# BiodataFeatherProMicro_004.net
KiCad netlist of a schematic drawn in EAGLE
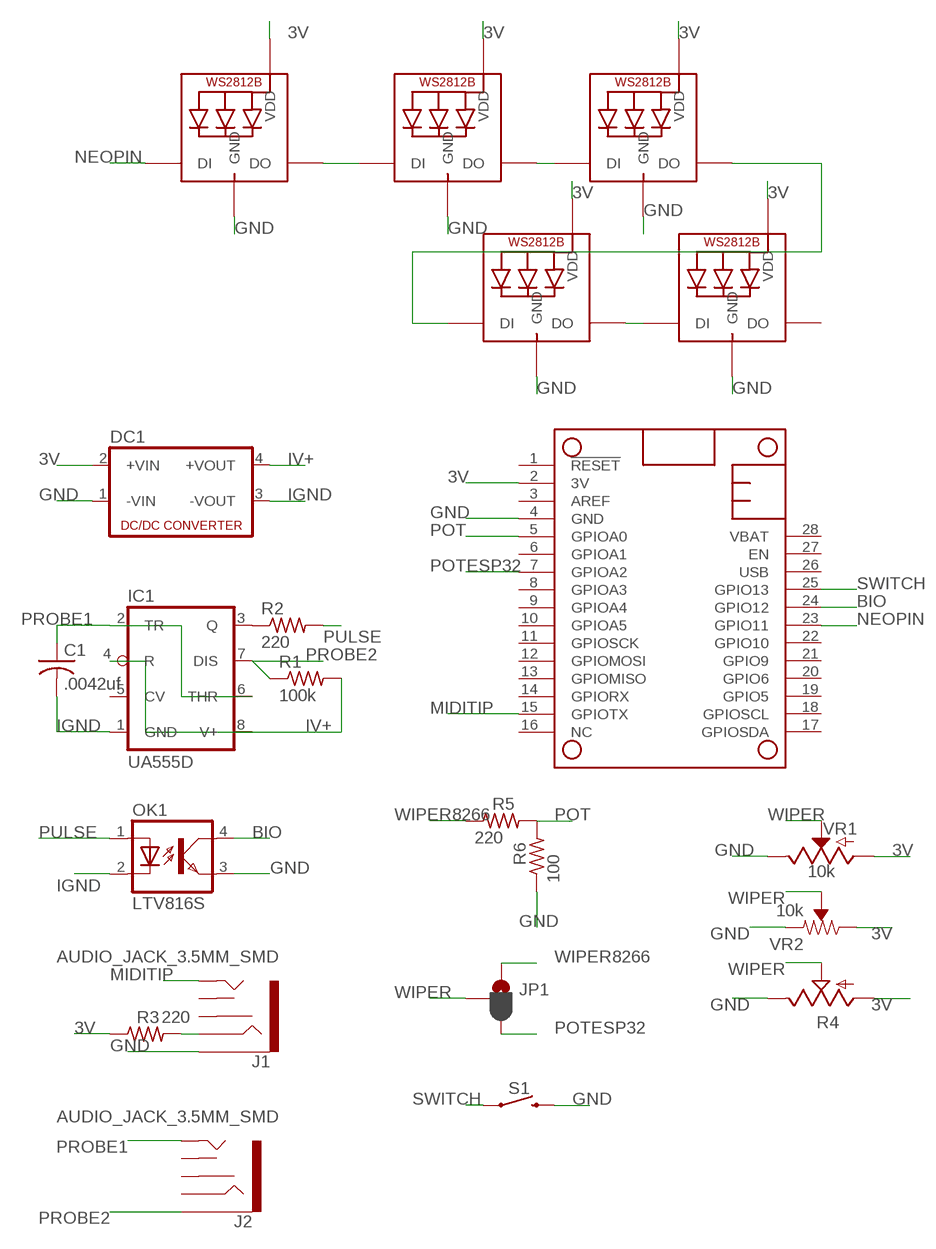
[diagram p0: schematic, sheet 1]

(export (version "E")
  (design (tool "Eeschema 10.0.6"))
  (components
    (comp (ref "C1")
      (value ".0042uf")
      (footprint "eagle-import:C1206")
      (libsource (lib "eagle-import") (part "C-USC1206"))
    )
    (comp (ref "DC1")
      (value "NME")
      (footprint "eagle-import:NME")
      (fields (field (name "MF") "C & D TECHNOLOGIES, INC") (field (name "MPN") "NME1205D"))
      (libsource (lib "eagle-import") (part "NME"))
    )
    (comp (ref "IC1")
      (value "UA555D")
      (footprint "eagle-import:SO08")
      (libsource (lib "eagle-import") (part "555DUA"))
    )
    (comp (ref "J1")
      (value "AUDIO_JACK_3.5MM_SMD")
      (footprint "eagle-import:AUDIO-JACK-3.5MM-SMD")
      (libsource (lib "eagle-import") (part "AUDIO_JACK_3.5MM_SMD"))
    )
    (comp (ref "J2")
      (value "AUDIO_JACK_3.5MM_SMD")
      (footprint "eagle-import:AUDIO-JACK-3.5MM-SMD")
      (libsource (lib "eagle-import") (part "AUDIO_JACK_3.5MM_SMD"))
    )
    (comp (ref "JP1")
      (value "JUMPER-SMT_3_1-NC_PASTE_SILK")
      (footprint "eagle-import:SMT-JUMPER_3_1-NC_PASTE_SILK")
      (libsource (lib "eagle-import") (part "JUMPER-SMT_3_1-NC_PASTE_SILK"))
    )
    (comp (ref "LED1")
      (value "WS2812B5050")
      (footprint "eagle-import:WS2812B")
      (libsource (lib "eagle-import") (part "WS2812B5050"))
    )
    (comp (ref "LED2")
      (value "WS2812B5050")
      (footprint "eagle-import:WS2812B")
      (libsource (lib "eagle-import") (part "WS2812B5050"))
    )
    (comp (ref "LED3")
      (value "WS2812B5050")
      (footprint "eagle-import:WS2812B")
      (libsource (lib "eagle-import") (part "WS2812B5050"))
    )
    (comp (ref "LED4")
      (value "WS2812B5050")
      (footprint "eagle-import:WS2812B")
      (libsource (lib "eagle-import") (part "WS2812B5050"))
    )
    (comp (ref "LED5")
      (value "WS2812B5050")
      (footprint "eagle-import:WS2812B")
      (libsource (lib "eagle-import") (part "WS2812B5050"))
    )
    (comp (ref "MS1")
      (value "FEATHERWING")
      (footprint "eagle-import:FEATHERWING_NOHOLES")
      (libsource (lib "eagle-import") (part "FEATHERWING"))
    )
    (comp (ref "OK1")
      (value "LTV816S")
      (footprint "eagle-import:SMD4")
      (libsource (lib "eagle-import") (part "LTV816S"))
    )
    (comp (ref "R1")
      (value "100k")
      (footprint "eagle-import:M1206")
      (libsource (lib "eagle-import") (part "R-US_M1206"))
    )
    (comp (ref "R2")
      (value "220")
      (footprint "eagle-import:M1206")
      (libsource (lib "eagle-import") (part "R-US_M1206"))
    )
    (comp (ref "R3")
      (value "220")
      (footprint "eagle-import:M1206")
      (libsource (lib "eagle-import") (part "R-US_M1206"))
    )
    (comp (ref "R4")
      (value "TRIM_US-S63P")
      (footprint "eagle-import:S63P")
      (libsource (lib "eagle-import") (part "TRIM_US-S63P"))
    )
    (comp (ref "R5")
      (value "220")
      (footprint "eagle-import:M1206")
      (libsource (lib "eagle-import") (part "R-US_M1206"))
    )
    (comp (ref "R6")
      (value "100")
      (footprint "eagle-import:M1206")
      (libsource (lib "eagle-import") (part "R-US_M1206"))
    )
    (comp (ref "S1")
      (value "MOMENTARY-SWITCH-SPST-PTH-6.0MM")
      (footprint "eagle-import:TACTILE_SWITCH_PTH_6.0MM")
      (libsource (lib "eagle-import") (part "MOMENTARY-SWITCH-SPST-PTH-6.0MM"))
    )
    (comp (ref "VR1")
      (value "10k")
      (footprint "eagle-import:POT-PTH-ALPS-KIT")
      (libsource (lib "eagle-import") (part "POTENTIOMETER-PTH-9MM-1/20W-20%-KIT"))
    )
    (comp (ref "VR2")
      (value "10k")
      (footprint "eagle-import:TRIMPOT-PTH-3386U")
      (libsource (lib "eagle-import") (part "TRIMPOT-PTH-10MM-KNOB-1/2W-10%"))
    )
  )
  (nets
    (net (code "1") (name "/3V") (class "Default")
      (node (ref "DC1") (pin "2") (pinfunction "+VIN_2") (pintype "passive"))
      (node (ref "LED1") (pin "1-VDD") (pinfunction "VDD_1-VDD") (pintype "power_in"))
      (node (ref "LED2") (pin "1-VDD") (pinfunction "VDD_1-VDD") (pintype "power_in"))
      (node (ref "LED3") (pin "1-VDD") (pinfunction "VDD_1-VDD") (pintype "power_in"))
      (node (ref "LED4") (pin "1-VDD") (pinfunction "VDD_1-VDD") (pintype "power_in"))
      (node (ref "LED5") (pin "1-VDD") (pinfunction "VDD_1-VDD") (pintype "power_in"))
      (node (ref "MS1") (pin "2") (pinfunction "3V_2") (pintype "power_in"))
      (node (ref "R3") (pin "1") (pinfunction "1_1") (pintype "passive"))
      (node (ref "R4") (pin "A") (pinfunction "A_A") (pintype "passive"))
      (node (ref "VR1") (pin "P$3") (pinfunction "A_P$3") (pintype "passive"))
      (node (ref "VR2") (pin "3") (pinfunction "CW_3") (pintype "passive"))
    )
    (net (code "2") (name "/BIO") (class "Default")
      (node (ref "MS1") (pin "24") (pinfunction "GPIO12_24") (pintype "bidirectional"))
      (node (ref "OK1") (pin "4") (pinfunction "COL_4") (pintype "passive"))
    )
    (net (code "3") (name "/GND") (class "Default")
      (node (ref "DC1") (pin "1") (pinfunction "-VIN_1") (pintype "passive"))
      (node (ref "J1") (pin "SLEEVE") (pinfunction "SLEEVE_SLEEVE") (pintype "bidirectional"))
      (node (ref "LED1") (pin "3-GND") (pinfunction "GND_3-GND") (pintype "power_in"))
      (node (ref "LED2") (pin "3-GND") (pinfunction "GND_3-GND") (pintype "power_in"))
      (node (ref "LED3") (pin "3-GND") (pinfunction "GND_3-GND") (pintype "power_in"))
      (node (ref "LED4") (pin "3-GND") (pinfunction "GND_3-GND") (pintype "power_in"))
      (node (ref "LED5") (pin "3-GND") (pinfunction "GND_3-GND") (pintype "power_in"))
      (node (ref "MS1") (pin "4") (pinfunction "GND_4") (pintype "power_in"))
      (node (ref "OK1") (pin "3") (pinfunction "EMIT_3") (pintype "passive"))
      (node (ref "R4") (pin "E") (pinfunction "E_E") (pintype "passive"))
      (node (ref "R6") (pin "1") (pinfunction "1_1") (pintype "passive"))
      (node (ref "S1") (pin "3") (pinfunction "2_3") (pintype "passive"))
      (node (ref "VR1") (pin "P$1") (pinfunction "E_P$1") (pintype "passive"))
      (node (ref "VR2") (pin "1") (pinfunction "CCW_1") (pintype "passive"))
    )
    (net (code "4") (name "/IGND") (class "Default")
      (node (ref "C1") (pin "2") (pinfunction "2_2") (pintype "passive"))
      (node (ref "DC1") (pin "3") (pinfunction "-VOUT_3") (pintype "passive"))
      (node (ref "IC1") (pin "1") (pinfunction "GND_1") (pintype "power_in"))
      (node (ref "OK1") (pin "2") (pinfunction "C_2") (pintype "passive"))
    )
    (net (code "5") (name "/IV+") (class "Default")
      (node (ref "DC1") (pin "4") (pinfunction "+VOUT_4") (pintype "passive"))
      (node (ref "IC1") (pin "4") (pinfunction "R_4") (pintype "input"))
      (node (ref "IC1") (pin "8") (pinfunction "V+_8") (pintype "power_in"))
      (node (ref "R1") (pin "2") (pinfunction "2_2") (pintype "passive"))
    )
    (net (code "6") (name "/MIDITIP") (class "Default")
      (node (ref "J1") (pin "TIP") (pinfunction "TIP_TIP") (pintype "bidirectional"))
      (node (ref "MS1") (pin "15") (pinfunction "GPIOTX_15") (pintype "bidirectional"))
    )
    (net (code "7") (name "/NEOPIN") (class "Default")
      (node (ref "LED1") (pin "4-DIN") (pinfunction "DI_4-DIN") (pintype "input"))
      (node (ref "MS1") (pin "23") (pinfunction "GPIO11_23") (pintype "bidirectional"))
    )
    (net (code "8") (name "/POT") (class "Default")
      (node (ref "MS1") (pin "5") (pinfunction "GPIOA0_5") (pintype "bidirectional"))
      (node (ref "R5") (pin "2") (pinfunction "2_2") (pintype "passive"))
      (node (ref "R6") (pin "2") (pinfunction "2_2") (pintype "passive"))
    )
    (net (code "9") (name "/POTESP32") (class "Default")
      (node (ref "JP1") (pin "3") (pinfunction "3_3") (pintype "passive"))
      (node (ref "MS1") (pin "7") (pinfunction "GPIOA2_7") (pintype "bidirectional"))
    )
    (net (code "10") (name "/PROBE1") (class "Default")
      (node (ref "C1") (pin "1") (pinfunction "1_1") (pintype "passive"))
      (node (ref "IC1") (pin "2") (pinfunction "TR_2") (pintype "input"))
      (node (ref "IC1") (pin "6") (pinfunction "THR_6") (pintype "input"))
      (node (ref "J2") (pin "TIP") (pinfunction "TIP_TIP") (pintype "bidirectional"))
    )
    (net (code "11") (name "/PROBE2") (class "Default")
      (node (ref "IC1") (pin "7") (pinfunction "DIS_7") (pintype "input"))
      (node (ref "J2") (pin "SLEEVE") (pinfunction "SLEEVE_SLEEVE") (pintype "bidirectional"))
      (node (ref "R1") (pin "1") (pinfunction "1_1") (pintype "passive"))
    )
    (net (code "12") (name "/PULSE") (class "Default")
      (node (ref "OK1") (pin "1") (pinfunction "A_1") (pintype "passive"))
      (node (ref "R2") (pin "2") (pinfunction "2_2") (pintype "passive"))
    )
    (net (code "13") (name "/SWITCH") (class "Default")
      (node (ref "MS1") (pin "25") (pinfunction "GPIO13_25") (pintype "bidirectional"))
      (node (ref "S1") (pin "1") (pinfunction "1_1") (pintype "passive"))
    )
    (net (code "14") (name "/USB") (class "Default")
      (node (ref "MS1") (pin "26") (pinfunction "USB_26") (pintype "power_in"))
    )
    (net (code "15") (name "/VBAT") (class "Default")
      (node (ref "MS1") (pin "28") (pinfunction "VBAT_28") (pintype "power_in"))
    )
    (net (code "16") (name "/WIPER") (class "Default")
      (node (ref "JP1") (pin "2") (pinfunction "2_2") (pintype "passive"))
      (node (ref "R4") (pin "S") (pinfunction "S_S") (pintype "passive"))
      (node (ref "VR1") (pin "P$2") (pinfunction "S_P$2") (pintype "passive"))
      (node (ref "VR2") (pin "2") (pinfunction "WIPER_2") (pintype "passive"))
    )
    (net (code "17") (name "/WIPER8266") (class "Default")
      (node (ref "JP1") (pin "1") (pinfunction "1_1") (pintype "passive"))
      (node (ref "R5") (pin "1") (pinfunction "1_1") (pintype "passive"))
    )
    (net (code "18") (name "Net-(IC1-Q)") (class "Default")
      (node (ref "IC1") (pin "3") (pinfunction "Q_3") (pintype "output"))
      (node (ref "R2") (pin "1") (pinfunction "1_1") (pintype "passive"))
    )
    (net (code "19") (name "Net-(J1-PadRING)") (class "Default")
      (node (ref "J1") (pin "RING") (pinfunction "RING_RING") (pintype "bidirectional"))
      (node (ref "R3") (pin "2") (pinfunction "2_2") (pintype "passive"))
    )
    (net (code "20") (name "Net-(LED1-DO)") (class "Default")
      (node (ref "LED1") (pin "2-DOUT") (pinfunction "DO_2-DOUT") (pintype "output"))
      (node (ref "LED2") (pin "4-DIN") (pinfunction "DI_4-DIN") (pintype "input"))
    )
    (net (code "21") (name "Net-(LED2-DO)") (class "Default")
      (node (ref "LED2") (pin "2-DOUT") (pinfunction "DO_2-DOUT") (pintype "output"))
      (node (ref "LED3") (pin "4-DIN") (pinfunction "DI_4-DIN") (pintype "input"))
    )
    (net (code "22") (name "Net-(LED3-DO)") (class "Default")
      (node (ref "LED3") (pin "2-DOUT") (pinfunction "DO_2-DOUT") (pintype "output"))
      (node (ref "LED4") (pin "4-DIN") (pinfunction "DI_4-DIN") (pintype "input"))
    )
    (net (code "23") (name "Net-(LED4-DO)") (class "Default")
      (node (ref "LED4") (pin "2-DOUT") (pinfunction "DO_2-DOUT") (pintype "output"))
      (node (ref "LED5") (pin "4-DIN") (pinfunction "DI_4-DIN") (pintype "input"))
    )
    (net (code "24") (name "unconnected-(IC1-CV-Pad5)") (class "Default")
      (node (ref "IC1") (pin "5") (pinfunction "CV_5") (pintype "input"))
    )
    (net (code "25") (name "unconnected-(J1-PadRSH)") (class "Default")
      (node (ref "J1") (pin "RSH") (pinfunction "RSH_RSH") (pintype "bidirectional"))
    )
    (net (code "26") (name "unconnected-(J1-PadTSH)") (class "Default")
      (node (ref "J1") (pin "TSH") (pinfunction "TSH_TSH") (pintype "bidirectional"))
    )
    (net (code "27") (name "unconnected-(J2-PadRING)") (class "Default")
      (node (ref "J2") (pin "RING") (pinfunction "RING_RING") (pintype "bidirectional"))
    )
    (net (code "28") (name "unconnected-(J2-PadRSH)") (class "Default")
      (node (ref "J2") (pin "RSH") (pinfunction "RSH_RSH") (pintype "bidirectional"))
    )
    (net (code "29") (name "unconnected-(J2-PadTSH)") (class "Default")
      (node (ref "J2") (pin "TSH") (pinfunction "TSH_TSH") (pintype "bidirectional"))
    )
    (net (code "30") (name "unconnected-(LED5-DO-Pad2-DOUT)") (class "Default")
      (node (ref "LED5") (pin "2-DOUT") (pinfunction "DO_2-DOUT") (pintype "output"))
    )
    (net (code "31") (name "unconnected-(MS1-AREF-Pad3)") (class "Default")
      (node (ref "MS1") (pin "3") (pinfunction "AREF_3") (pintype "passive"))
    )
    (net (code "32") (name "unconnected-(MS1-EN-Pad27)") (class "Default")
      (node (ref "MS1") (pin "27") (pinfunction "EN_27") (pintype "passive"))
    )
    (net (code "33") (name "unconnected-(MS1-GPIO5-Pad19)") (class "Default")
      (node (ref "MS1") (pin "19") (pinfunction "GPIO5_19") (pintype "bidirectional"))
    )
    (net (code "34") (name "unconnected-(MS1-GPIO6-Pad20)") (class "Default")
      (node (ref "MS1") (pin "20") (pinfunction "GPIO6_20") (pintype "bidirectional"))
    )
    (net (code "35") (name "unconnected-(MS1-GPIO9-Pad21)") (class "Default")
      (node (ref "MS1") (pin "21") (pinfunction "GPIO9_21") (pintype "bidirectional"))
    )
    (net (code "36") (name "unconnected-(MS1-GPIO10-Pad22)") (class "Default")
      (node (ref "MS1") (pin "22") (pinfunction "GPIO10_22") (pintype "bidirectional"))
    )
    (net (code "37") (name "unconnected-(MS1-GPIOA1-Pad6)") (class "Default")
      (node (ref "MS1") (pin "6") (pinfunction "GPIOA1_6") (pintype "bidirectional"))
    )
    (net (code "38") (name "unconnected-(MS1-GPIOA3-Pad8)") (class "Default")
      (node (ref "MS1") (pin "8") (pinfunction "GPIOA3_8") (pintype "bidirectional"))
    )
    (net (code "39") (name "unconnected-(MS1-GPIOA4-Pad9)") (class "Default")
      (node (ref "MS1") (pin "9") (pinfunction "GPIOA4_9") (pintype "bidirectional"))
    )
    (net (code "40") (name "unconnected-(MS1-GPIOA5-Pad10)") (class "Default")
      (node (ref "MS1") (pin "10") (pinfunction "GPIOA5_10") (pintype "bidirectional"))
    )
    (net (code "41") (name "unconnected-(MS1-GPIOMISO-Pad13)") (class "Default")
      (node (ref "MS1") (pin "13") (pinfunction "GPIOMISO_13") (pintype "bidirectional"))
    )
    (net (code "42") (name "unconnected-(MS1-GPIOMOSI-Pad12)") (class "Default")
      (node (ref "MS1") (pin "12") (pinfunction "GPIOMOSI_12") (pintype "bidirectional"))
    )
    (net (code "43") (name "unconnected-(MS1-GPIORX-Pad14)") (class "Default")
      (node (ref "MS1") (pin "14") (pinfunction "GPIORX_14") (pintype "bidirectional"))
    )
    (net (code "44") (name "unconnected-(MS1-GPIOSCK-Pad11)") (class "Default")
      (node (ref "MS1") (pin "11") (pinfunction "GPIOSCK_11") (pintype "bidirectional"))
    )
    (net (code "45") (name "unconnected-(MS1-GPIOSCL-Pad18)") (class "Default")
      (node (ref "MS1") (pin "18") (pinfunction "GPIOSCL_18") (pintype "bidirectional"))
    )
    (net (code "46") (name "unconnected-(MS1-GPIOSDA-Pad17)") (class "Default")
      (node (ref "MS1") (pin "17") (pinfunction "GPIOSDA_17") (pintype "bidirectional"))
    )
    (net (code "47") (name "unconnected-(MS1-NC-Pad16)") (class "Default")
      (node (ref "MS1") (pin "16") (pinfunction "NC_16") (pintype "passive"))
    )
    (net (code "48") (name "unconnected-(MS1-~{RESET}-Pad1)") (class "Default")
      (node (ref "MS1") (pin "1") (pinfunction "~{RESET}_1") (pintype "input"))
    )
  )
)
